# PCB.net
KiCad netlist of a schematic drawn in EAGLE
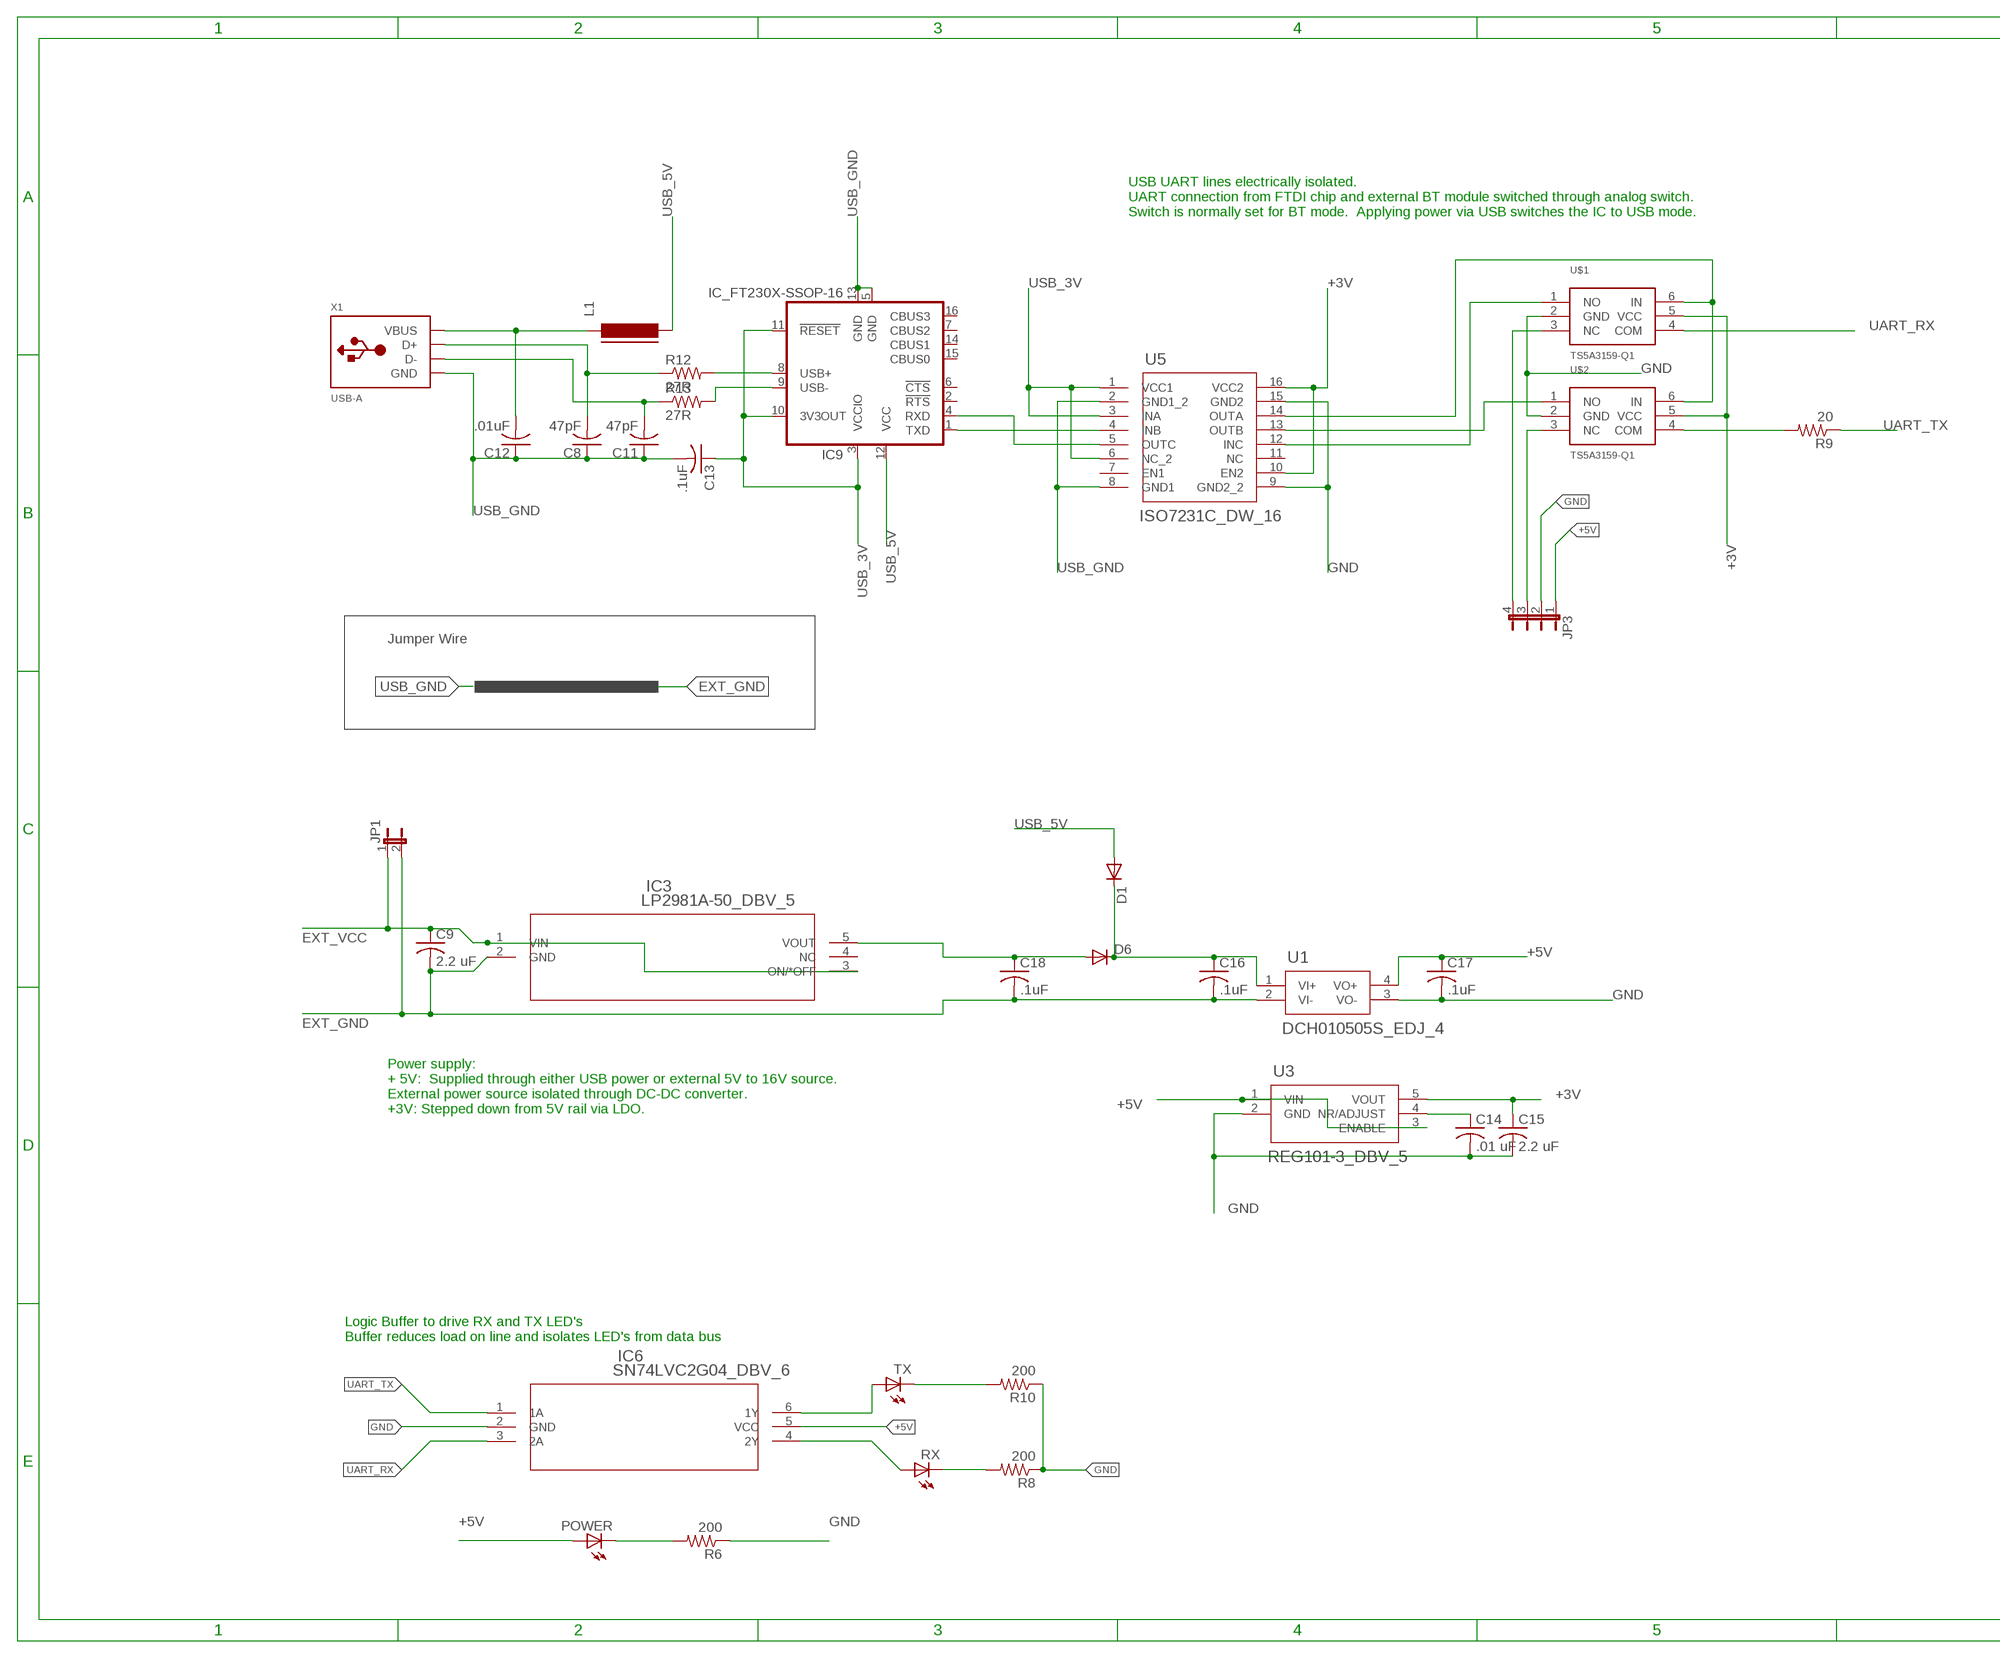
[diagram p0: schematic, sheet 1, part 1 of 2]
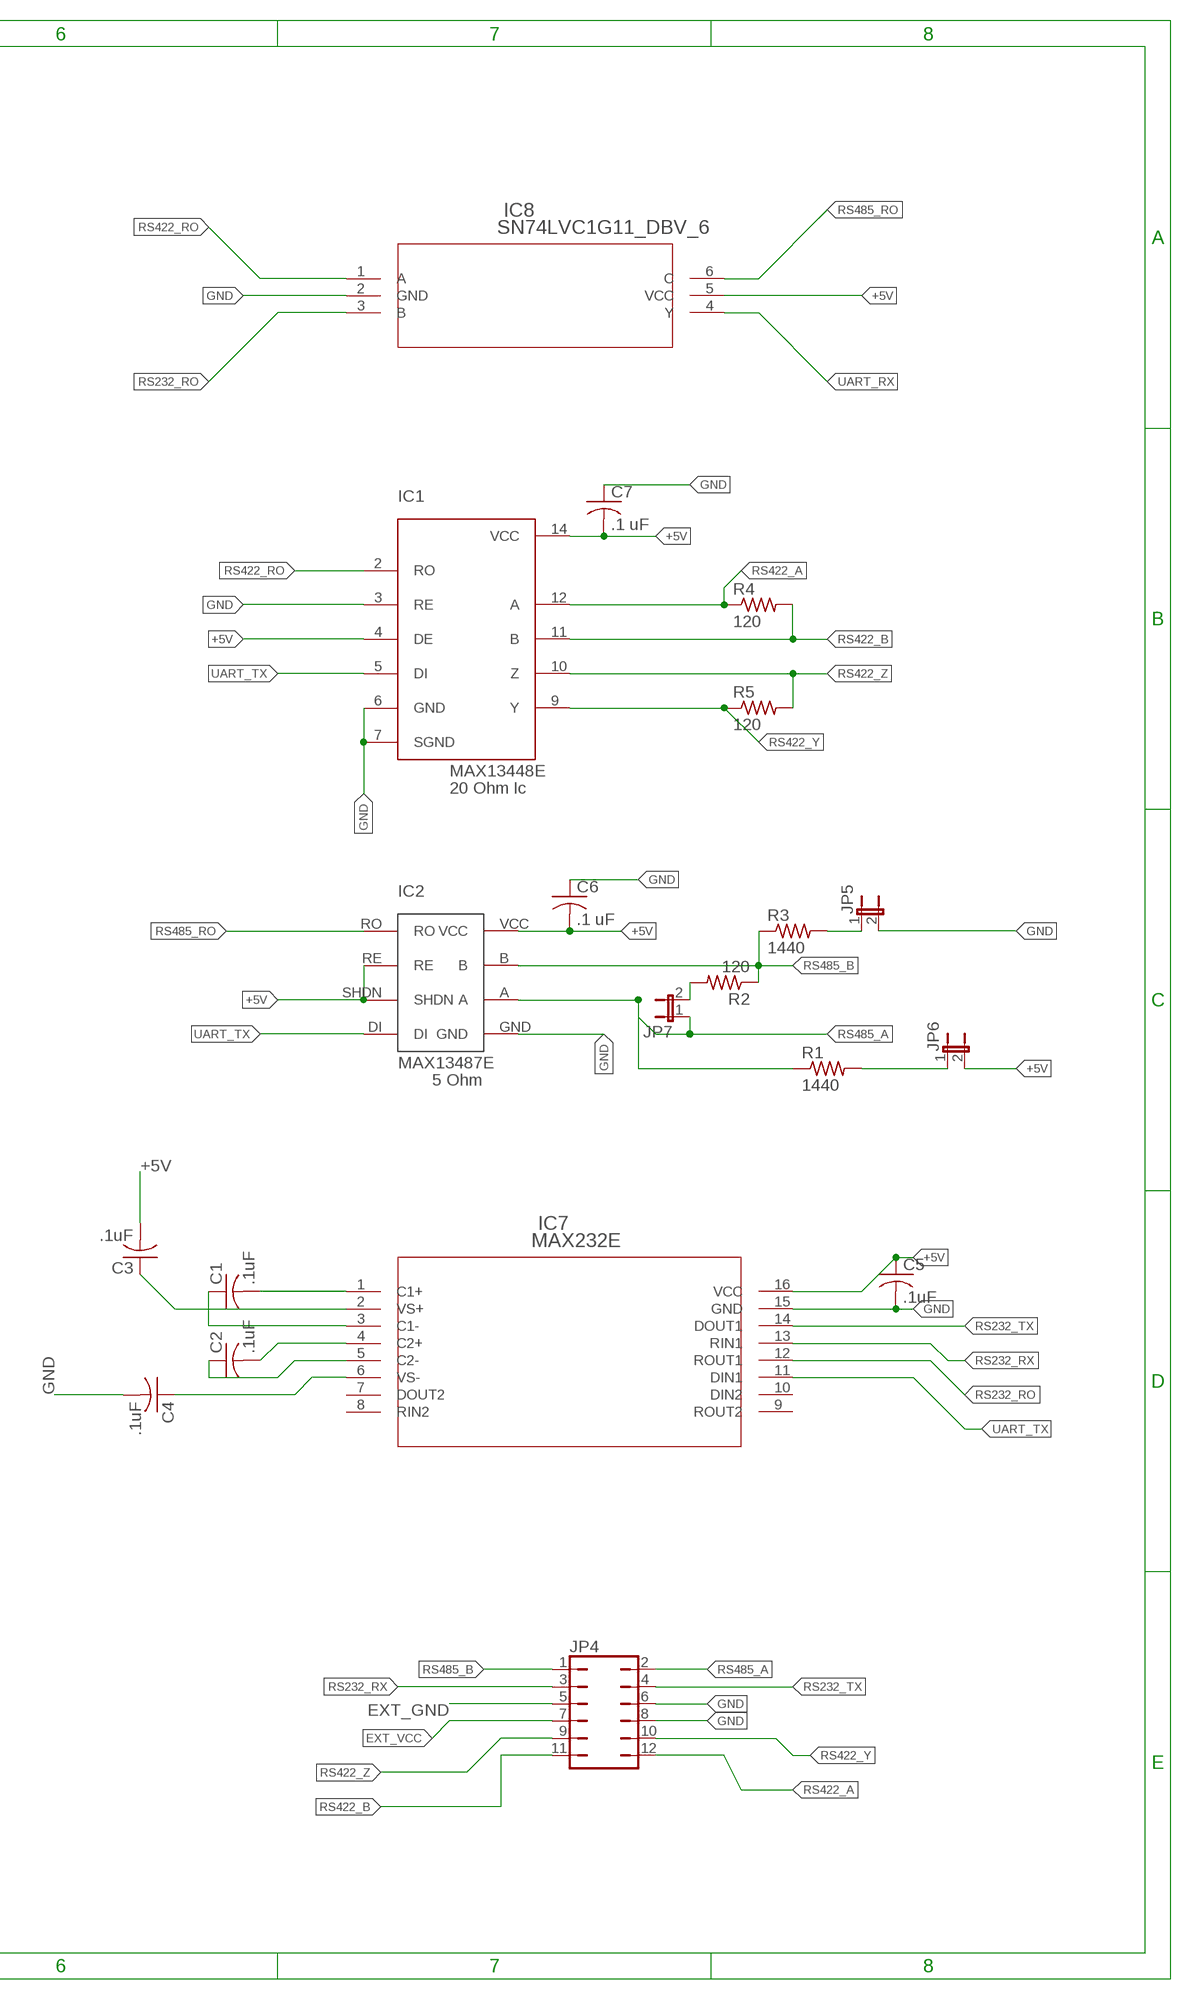
[diagram p1: schematic, sheet 1, part 2 of 2]

(export (version "E")
  (design (tool "Eeschema 10.0.6"))
  (components
    (comp (ref "C1")
      (value ".1uF")
      (footprint "eagle-import:C1206")
      (libsource (lib "eagle-import") (part "C-USC1206"))
    )
    (comp (ref "C2")
      (value ".1uF")
      (footprint "eagle-import:C1206")
      (libsource (lib "eagle-import") (part "C-USC1206"))
    )
    (comp (ref "C3")
      (value ".1uF")
      (footprint "eagle-import:C1206")
      (libsource (lib "eagle-import") (part "C-USC1206"))
    )
    (comp (ref "C4")
      (value ".1uF")
      (footprint "eagle-import:C1206")
      (libsource (lib "eagle-import") (part "C-USC1206"))
    )
    (comp (ref "C5")
      (value ".1uF")
      (footprint "eagle-import:C1206")
      (libsource (lib "eagle-import") (part "C-USC1206"))
    )
    (comp (ref "C6")
      (value ".1 uF")
      (footprint "eagle-import:C1206")
      (libsource (lib "eagle-import") (part "C-USC1206"))
    )
    (comp (ref "C7")
      (value ".1 uF")
      (footprint "eagle-import:C1206")
      (libsource (lib "eagle-import") (part "C-USC1206"))
    )
    (comp (ref "C8")
      (value "47pF")
      (footprint "eagle-import:C1206")
      (libsource (lib "eagle-import") (part "C-USC1206"))
    )
    (comp (ref "C9")
      (value "2.2 uF")
      (footprint "eagle-import:C1206")
      (libsource (lib "eagle-import") (part "C-USC1206"))
    )
    (comp (ref "C11")
      (value "47pF")
      (footprint "eagle-import:C1206")
      (libsource (lib "eagle-import") (part "C-USC1206"))
    )
    (comp (ref "C12")
      (value ".01uF")
      (footprint "eagle-import:C1206")
      (libsource (lib "eagle-import") (part "C-USC1206"))
    )
    (comp (ref "C13")
      (value ".1uF")
      (footprint "eagle-import:C1206")
      (libsource (lib "eagle-import") (part "C-USC1206"))
    )
    (comp (ref "C14")
      (value ".01 uF")
      (footprint "eagle-import:C1206")
      (libsource (lib "eagle-import") (part "C-USC1206"))
    )
    (comp (ref "C15")
      (value "2.2 uF")
      (footprint "eagle-import:C1206")
      (libsource (lib "eagle-import") (part "C-USC1206"))
    )
    (comp (ref "C16")
      (value ".1uF")
      (footprint "eagle-import:C1206")
      (libsource (lib "eagle-import") (part "C-USC1206"))
    )
    (comp (ref "C17")
      (value ".1uF")
      (footprint "eagle-import:C1206")
      (libsource (lib "eagle-import") (part "C-USC1206"))
    )
    (comp (ref "C18")
      (value ".1uF")
      (footprint "eagle-import:C1206")
      (libsource (lib "eagle-import") (part "C-USC1206"))
    )
    (comp (ref "D1")
      (value "DIODE-SOT23")
      (footprint "eagle-import:SOT-23")
      (libsource (lib "eagle-import") (part "DIODE-SOT23"))
    )
    (comp (ref "D6")
      (value "DIODE-SOT23")
      (footprint "eagle-import:SOT-23")
      (libsource (lib "eagle-import") (part "DIODE-SOT23"))
    )
    (comp (ref "IC1")
      (value "MAX13448E")
      (footprint "eagle-import:SO14(N)")
      (libsource (lib "eagle-import") (part "MAX13448E"))
    )
    (comp (ref "IC2")
      (value "MAX13487E")
      (footprint "eagle-import:MAX13487E")
      (libsource (lib "eagle-import") (part "MAX13487E"))
    )
    (comp (ref "IC3")
      (value "LP2981A-50_DBV_5")
      (footprint "eagle-import:DBV5")
      (fields
        (field (name "GENERIC_PART_NUMBER") "LP2981A-50")
        (field (name "MANUFACTURER") "Texas Instruments")
        (field (name "MANUFACTURER_PART_NUMBER") "lp2981a-50_dbv_5")
      )
      (libsource (lib "eagle-import") (part "LP2981A-50_DBV_5"))
    )
    (comp (ref "IC6")
      (value "SN74LVC2G04_DBV_6")
      (footprint "eagle-import:DBV6")
      (fields
        (field (name "GENERIC_PART_NUMBER") "SN74LVC2G04")
        (field (name "MANUFACTURER") "Texas Instruments")
        (field (name "MANUFACTURER_PART_NUMBER") "sn74lvc2g04_dbv_6")
      )
      (libsource (lib "eagle-import") (part "SN74LVC2G04_DBV_6"))
    )
    (comp (ref "IC7")
      (value "MAX232E")
      (footprint "eagle-import:D16")
      (fields
        (field (name "MANUFACTURER") "Texas Instruments")
        (field (name "MANUFACTURER_PART_NUMBER") "max232e_d_16")
      )
      (libsource (lib "eagle-import") (part "MAX232E_D_16"))
    )
    (comp (ref "IC8")
      (value "SN74LVC1G11_DBV_6")
      (footprint "eagle-import:DBV6")
      (fields
        (field (name "GENERIC_PART_NUMBER") "SN74LVC1G11")
        (field (name "MANUFACTURER") "Texas Instruments")
        (field (name "MANUFACTURER_PART_NUMBER") "sn74lvc1g11_dbv_6")
      )
      (libsource (lib "eagle-import") (part "SN74LVC1G11_DBV_6"))
    )
    (comp (ref "IC9")
      (value "IC_FT230X-SSOP-16")
      (footprint "eagle-import:SSOP-16-FTDI")
      (libsource (lib "eagle-import") (part "IC_FT230X-SSOP-16"))
    )
    (comp (ref "JP1")
      (value "JP1E")
      (footprint "eagle-import:JP1")
      (libsource (lib "eagle-import") (part "JP1E"))
    )
    (comp (ref "JP3")
      (value "JP4E")
      (footprint "eagle-import:JP4")
      (libsource (lib "eagle-import") (part "JP4E"))
    )
    (comp (ref "JP4")
      (value "JP6Q")
      (footprint "eagle-import:JP6Q")
      (libsource (lib "eagle-import") (part "JP6Q"))
    )
    (comp (ref "JP5")
      (value "JP1E")
      (footprint "eagle-import:JP1")
      (libsource (lib "eagle-import") (part "JP1E"))
    )
    (comp (ref "JP6")
      (value "JP1E")
      (footprint "eagle-import:JP1")
      (libsource (lib "eagle-import") (part "JP1E"))
    )
    (comp (ref "JP7")
      (value "JP1E")
      (footprint "eagle-import:JP1")
      (libsource (lib "eagle-import") (part "JP1E"))
    )
    (comp (ref "L1")
      (value "FERRITE-1206")
      (footprint "eagle-import:FB1206")
      (libsource (lib "eagle-import") (part "FERRITE-1206"))
    )
    (comp (ref "POWER")
      (value "LEDSMT1206")
      (footprint "eagle-import:1206")
      (libsource (lib "eagle-import") (part "LEDSMT1206"))
    )
    (comp (ref "R1")
      (value "1440")
      (footprint "eagle-import:M1206")
      (libsource (lib "eagle-import") (part "R-US_M1206"))
    )
    (comp (ref "R2")
      (value "120")
      (footprint "eagle-import:M1206")
      (libsource (lib "eagle-import") (part "R-US_M1206"))
    )
    (comp (ref "R3")
      (value "1440")
      (footprint "eagle-import:M1206")
      (libsource (lib "eagle-import") (part "R-US_M1206"))
    )
    (comp (ref "R4")
      (value "120")
      (footprint "eagle-import:R1206")
      (libsource (lib "eagle-import") (part "R-US_R1206"))
    )
    (comp (ref "R5")
      (value "120")
      (footprint "eagle-import:R1206")
      (libsource (lib "eagle-import") (part "R-US_R1206"))
    )
    (comp (ref "R6")
      (value "200")
      (footprint "eagle-import:M1206")
      (libsource (lib "eagle-import") (part "R-US_M1206"))
    )
    (comp (ref "R8")
      (value "200")
      (footprint "eagle-import:M1206")
      (libsource (lib "eagle-import") (part "R-US_M1206"))
    )
    (comp (ref "R9")
      (value "20")
      (footprint "eagle-import:M1206")
      (libsource (lib "eagle-import") (part "R-US_M1206"))
    )
    (comp (ref "R10")
      (value "200")
      (footprint "eagle-import:M1206")
      (libsource (lib "eagle-import") (part "R-US_M1206"))
    )
    (comp (ref "R12")
      (value "27R")
      (footprint "eagle-import:R1206")
      (libsource (lib "eagle-import") (part "R-US_R1206"))
    )
    (comp (ref "R13")
      (value "27R")
      (footprint "eagle-import:R1206")
      (libsource (lib "eagle-import") (part "R-US_R1206"))
    )
    (comp (ref "RX")
      (value "LEDSMT1206")
      (footprint "eagle-import:1206")
      (libsource (lib "eagle-import") (part "LEDSMT1206"))
    )
    (comp (ref "TX")
      (value "LEDSMT1206")
      (footprint "eagle-import:1206")
      (libsource (lib "eagle-import") (part "LEDSMT1206"))
    )
    (comp (ref "U$1")
      (value "TS5A3159-Q1")
      (footprint "eagle-import:DBV6")
      (libsource (lib "eagle-import") (part "TS5A3159-Q1"))
    )
    (comp (ref "U$2")
      (value "TS5A3159-Q1")
      (footprint "eagle-import:DBV6")
      (libsource (lib "eagle-import") (part "TS5A3159-Q1"))
    )
    (comp (ref "U1")
      (value "DCH010505S_EDJ_4")
      (footprint "eagle-import:EDJ4")
      (fields
        (field (name "GENERIC_PART_NUMBER") "DCH010505S")
        (field (name "MANUFACTURER") "Texas Instruments")
        (field (name "MANUFACTURER_PART_NUMBER") "dch010505s_edj_4")
      )
      (libsource (lib "eagle-import") (part "DCH010505S_EDJ_4"))
    )
    (comp (ref "U3")
      (value "REG101-3_DBV_5")
      (footprint "eagle-import:DBV5")
      (fields
        (field (name "GENERIC_PART_NUMBER") "REG101-3")
        (field (name "MANUFACTURER") "Texas Instruments")
        (field (name "MANUFACTURER_PART_NUMBER") "reg101-3_dbv_5")
      )
      (libsource (lib "eagle-import") (part "REG101-3_DBV_5"))
    )
    (comp (ref "U5")
      (value "ISO7231C_DW_16")
      (footprint "eagle-import:DW16")
      (fields
        (field (name "GENERIC_PART_NUMBER") "ISO7231C")
        (field (name "MANUFACTURER") "Texas Instruments")
        (field (name "MANUFACTURER_PART_NUMBER") "iso7231c_dw_16")
      )
      (libsource (lib "eagle-import") (part "ISO7231C_DW_16"))
    )
    (comp (ref "X1")
      (value "USB-A")
      (footprint "eagle-import:MOLEX_480371000")
      (libsource (lib "eagle-import") (part "USB-A"))
    )
  )
  (nets
    (net (code "1") (name "+5V") (class "Default")
      (node (ref "C17") (pin "1") (pinfunction "1_1") (pintype "passive"))
      (node (ref "C3") (pin "2") (pinfunction "2_2") (pintype "passive"))
      (node (ref "C5") (pin "1") (pinfunction "1_1") (pintype "passive"))
      (node (ref "C6") (pin "2") (pinfunction "2_2") (pintype "passive"))
      (node (ref "C7") (pin "2") (pinfunction "2_2") (pintype "passive"))
      (node (ref "IC1") (pin "14") (pinfunction "VCC_14") (pintype "bidirectional"))
      (node (ref "IC1") (pin "4") (pinfunction "DE_4") (pintype "bidirectional"))
      (node (ref "IC2") (pin "RE") (pinfunction "RE_RE") (pintype "bidirectional"))
      (node (ref "IC2") (pin "SHDN") (pinfunction "SHDN_SHDN") (pintype "bidirectional"))
      (node (ref "IC2") (pin "VCC") (pinfunction "VCC_VCC") (pintype "bidirectional"))
      (node (ref "IC6") (pin "5") (pinfunction "VCC_5") (pintype "power_in"))
      (node (ref "IC7") (pin "16") (pinfunction "VCC_16") (pintype "power_in"))
      (node (ref "IC8") (pin "5") (pinfunction "VCC_5") (pintype "power_in"))
      (node (ref "JP3") (pin "1") (pinfunction "1_1") (pintype "passive"))
      (node (ref "JP6") (pin "2") (pinfunction "2_2") (pintype "passive"))
      (node (ref "POWER") (pin "A") (pinfunction "A_A") (pintype "passive"))
      (node (ref "U1") (pin "4") (pinfunction "VO+_4") (pintype "output"))
      (node (ref "U3") (pin "1") (pinfunction "VIN_1") (pintype "input"))
      (node (ref "U3") (pin "3") (pinfunction "ENABLE_3") (pintype "passive"))
    )
    (net (code "2") (name "/+3V") (class "Default")
      (node (ref "C15") (pin "1") (pinfunction "1_1") (pintype "passive"))
      (node (ref "U$1") (pin "5") (pinfunction "VCC_5") (pintype "power_in"))
      (node (ref "U$2") (pin "5") (pinfunction "VCC_5") (pintype "power_in"))
      (node (ref "U3") (pin "5") (pinfunction "VOUT_5") (pintype "output"))
      (node (ref "U5") (pin "10") (pinfunction "EN2_10") (pintype "passive"))
      (node (ref "U5") (pin "16") (pinfunction "VCC2_16") (pintype "power_in"))
    )
    (net (code "3") (name "/USB_3V") (class "Default")
      (node (ref "C13") (pin "1") (pinfunction "1_1") (pintype "passive"))
      (node (ref "IC9") (pin "10") (pinfunction "3V3OUT_10") (pintype "power_in"))
      (node (ref "IC9") (pin "11") (pinfunction "~{RESET}_11") (pintype "bidirectional"))
      (node (ref "IC9") (pin "3") (pinfunction "VCCIO_3") (pintype "power_in"))
      (node (ref "U5") (pin "1") (pinfunction "VCC1_1") (pintype "power_in"))
      (node (ref "U5") (pin "3") (pinfunction "INA_3") (pintype "input"))
      (node (ref "U5") (pin "6") (pinfunction "NC_2_6") (pintype "passive"))
    )
    (net (code "4") (name "/USB_5V") (class "Default")
      (node (ref "D1") (pin "1") (pinfunction "A_1") (pintype "passive"))
      (node (ref "IC9") (pin "12") (pinfunction "VCC_12") (pintype "power_in"))
      (node (ref "L1") (pin "2") (pinfunction "2_2") (pintype "passive"))
    )
    (net (code "5") (name "EXT_GND") (class "Default")
      (node (ref "C16") (pin "2") (pinfunction "2_2") (pintype "passive"))
      (node (ref "C18") (pin "2") (pinfunction "2_2") (pintype "passive"))
      (node (ref "C9") (pin "2") (pinfunction "2_2") (pintype "passive"))
      (node (ref "IC3") (pin "2") (pinfunction "GND_2") (pintype "power_in"))
      (node (ref "JP1") (pin "2") (pinfunction "2_2") (pintype "passive"))
      (node (ref "JP4") (pin "5") (pinfunction "5_5") (pintype "passive"))
      (node (ref "U1") (pin "2") (pinfunction "VI-_2") (pintype "input"))
    )
    (net (code "6") (name "EXT_VCC") (class "Default")
      (node (ref "C9") (pin "1") (pinfunction "1_1") (pintype "passive"))
      (node (ref "IC3") (pin "1") (pinfunction "VIN_1") (pintype "input"))
      (node (ref "IC3") (pin "3") (pinfunction "ON/*OFF_3") (pintype "passive"))
      (node (ref "JP1") (pin "1") (pinfunction "1_1") (pintype "passive"))
      (node (ref "JP4") (pin "7") (pinfunction "7_7") (pintype "passive"))
    )
    (net (code "7") (name "GND") (class "Default")
      (node (ref "C14") (pin "2") (pinfunction "2_2") (pintype "passive"))
      (node (ref "C15") (pin "2") (pinfunction "2_2") (pintype "passive"))
      (node (ref "C17") (pin "2") (pinfunction "2_2") (pintype "passive"))
      (node (ref "C4") (pin "2") (pinfunction "2_2") (pintype "passive"))
      (node (ref "C5") (pin "2") (pinfunction "2_2") (pintype "passive"))
      (node (ref "C6") (pin "1") (pinfunction "1_1") (pintype "passive"))
      (node (ref "C7") (pin "1") (pinfunction "1_1") (pintype "passive"))
      (node (ref "IC1") (pin "3") (pinfunction "RE_3") (pintype "bidirectional"))
      (node (ref "IC1") (pin "6") (pinfunction "GND_6") (pintype "bidirectional"))
      (node (ref "IC1") (pin "7") (pinfunction "SGND_7") (pintype "bidirectional"))
      (node (ref "IC2") (pin "GND") (pinfunction "GND_GND") (pintype "bidirectional"))
      (node (ref "IC6") (pin "2") (pinfunction "GND_2") (pintype "power_in"))
      (node (ref "IC7") (pin "15") (pinfunction "GND_15") (pintype "power_in"))
      (node (ref "IC8") (pin "2") (pinfunction "GND_2") (pintype "power_in"))
      (node (ref "JP3") (pin "2") (pinfunction "2_2") (pintype "passive"))
      (node (ref "JP4") (pin "6") (pinfunction "6_6") (pintype "passive"))
      (node (ref "JP4") (pin "8") (pinfunction "8_8") (pintype "passive"))
      (node (ref "JP5") (pin "2") (pinfunction "2_2") (pintype "passive"))
      (node (ref "R10") (pin "1") (pinfunction "1_1") (pintype "passive"))
      (node (ref "R6") (pin "1") (pinfunction "1_1") (pintype "passive"))
      (node (ref "R8") (pin "1") (pinfunction "1_1") (pintype "passive"))
      (node (ref "U$1") (pin "2") (pinfunction "GND_2") (pintype "power_in"))
      (node (ref "U$2") (pin "2") (pinfunction "GND_2") (pintype "power_in"))
      (node (ref "U1") (pin "3") (pinfunction "VO-_3") (pintype "output"))
      (node (ref "U3") (pin "2") (pinfunction "GND_2") (pintype "power_in"))
      (node (ref "U5") (pin "15") (pinfunction "GND2_15") (pintype "power_in"))
      (node (ref "U5") (pin "9") (pinfunction "GND2_2_9") (pintype "power_in"))
    )
    (net (code "8") (name "Net-(D1-C)") (class "Default")
      (node (ref "C16") (pin "1") (pinfunction "1_1") (pintype "passive"))
      (node (ref "D1") (pin "3") (pinfunction "C_3") (pintype "passive"))
      (node (ref "D6") (pin "3") (pinfunction "C_3") (pintype "passive"))
      (node (ref "U1") (pin "1") (pinfunction "VI+_1") (pintype "input"))
    )
    (net (code "9") (name "Net-(D6-A)") (class "Default")
      (node (ref "C18") (pin "1") (pinfunction "1_1") (pintype "passive"))
      (node (ref "D6") (pin "1") (pinfunction "A_1") (pintype "passive"))
      (node (ref "IC3") (pin "5") (pinfunction "VOUT_5") (pintype "output"))
    )
    (net (code "10") (name "Net-(IC6-1Y)") (class "Default")
      (node (ref "IC6") (pin "6") (pinfunction "1Y_6") (pintype "output"))
      (node (ref "TX") (pin "A") (pinfunction "A_A") (pintype "passive"))
    )
    (net (code "11") (name "Net-(IC6-2Y)") (class "Default")
      (node (ref "IC6") (pin "4") (pinfunction "2Y_4") (pintype "output"))
      (node (ref "RX") (pin "A") (pinfunction "A_A") (pintype "passive"))
    )
    (net (code "12") (name "Net-(IC7-C1+)") (class "Default")
      (node (ref "C1") (pin "2") (pinfunction "2_2") (pintype "passive"))
      (node (ref "IC7") (pin "1") (pinfunction "C1+_1") (pintype "passive"))
    )
    (net (code "13") (name "Net-(IC7-C1-)") (class "Default")
      (node (ref "C1") (pin "1") (pinfunction "1_1") (pintype "passive"))
      (node (ref "IC7") (pin "3") (pinfunction "C1-_3") (pintype "passive"))
    )
    (net (code "14") (name "Net-(IC7-C2+)") (class "Default")
      (node (ref "C2") (pin "2") (pinfunction "2_2") (pintype "passive"))
      (node (ref "IC7") (pin "4") (pinfunction "C2+_4") (pintype "passive"))
    )
    (net (code "15") (name "Net-(IC7-C2-)") (class "Default")
      (node (ref "C2") (pin "1") (pinfunction "1_1") (pintype "passive"))
      (node (ref "IC7") (pin "5") (pinfunction "C2-_5") (pintype "passive"))
    )
    (net (code "16") (name "Net-(IC7-VS+)") (class "Default")
      (node (ref "C3") (pin "1") (pinfunction "1_1") (pintype "passive"))
      (node (ref "IC7") (pin "2") (pinfunction "VS+_2") (pintype "power_in"))
    )
    (net (code "17") (name "Net-(IC7-VS-)") (class "Default")
      (node (ref "C4") (pin "1") (pinfunction "1_1") (pintype "passive"))
      (node (ref "IC7") (pin "6") (pinfunction "VS-_6") (pintype "power_in"))
    )
    (net (code "18") (name "Net-(IC9-RXD)") (class "Default")
      (node (ref "IC9") (pin "4") (pinfunction "RXD_4") (pintype "input"))
      (node (ref "U5") (pin "5") (pinfunction "OUTC_5") (pintype "output"))
    )
    (net (code "19") (name "Net-(IC9-TXD)") (class "Default")
      (node (ref "IC9") (pin "1") (pinfunction "TXD_1") (pintype "output"))
      (node (ref "U5") (pin "4") (pinfunction "INB_4") (pintype "input"))
    )
    (net (code "20") (name "Net-(IC9-USB+)") (class "Default")
      (node (ref "IC9") (pin "8") (pinfunction "USB+_8") (pintype "output"))
      (node (ref "R12") (pin "2") (pinfunction "2_2") (pintype "passive"))
    )
    (net (code "21") (name "Net-(IC9-USB-)") (class "Default")
      (node (ref "IC9") (pin "9") (pinfunction "USB-_9") (pintype "input"))
      (node (ref "R13") (pin "2") (pinfunction "2_2") (pintype "passive"))
    )
    (net (code "22") (name "Net-(JP5-Pad1)") (class "Default")
      (node (ref "JP5") (pin "1") (pinfunction "1_1") (pintype "passive"))
      (node (ref "R3") (pin "2") (pinfunction "2_2") (pintype "passive"))
    )
    (net (code "23") (name "Net-(JP6-Pad1)") (class "Default")
      (node (ref "JP6") (pin "1") (pinfunction "1_1") (pintype "passive"))
      (node (ref "R1") (pin "2") (pinfunction "2_2") (pintype "passive"))
    )
    (net (code "24") (name "Net-(JP7-Pad2)") (class "Default")
      (node (ref "JP7") (pin "2") (pinfunction "2_2") (pintype "passive"))
      (node (ref "R2") (pin "2") (pinfunction "2_2") (pintype "passive"))
    )
    (net (code "25") (name "Net-(POWER-PadC)") (class "Default")
      (node (ref "POWER") (pin "C") (pinfunction "C_C") (pintype "passive"))
      (node (ref "R6") (pin "2") (pinfunction "2_2") (pintype "passive"))
    )
    (net (code "26") (name "Net-(R8-Pad2)") (class "Default")
      (node (ref "R8") (pin "2") (pinfunction "2_2") (pintype "passive"))
      (node (ref "RX") (pin "C") (pinfunction "C_C") (pintype "passive"))
    )
    (net (code "27") (name "Net-(R10-Pad2)") (class "Default")
      (node (ref "R10") (pin "2") (pinfunction "2_2") (pintype "passive"))
      (node (ref "TX") (pin "C") (pinfunction "C_C") (pintype "passive"))
    )
    (net (code "28") (name "Net-(U$1-IN)") (class "Default")
      (node (ref "U$1") (pin "6") (pinfunction "IN_6") (pintype "power_in"))
      (node (ref "U$2") (pin "6") (pinfunction "IN_6") (pintype "power_in"))
      (node (ref "U5") (pin "14") (pinfunction "OUTA_14") (pintype "output"))
    )
    (net (code "29") (name "Net-(U$1-NC)") (class "Default")
      (node (ref "JP3") (pin "4") (pinfunction "4_4") (pintype "passive"))
      (node (ref "U$1") (pin "3") (pinfunction "NC_3") (pintype "power_in"))
    )
    (net (code "30") (name "Net-(U$1-NO)") (class "Default")
      (node (ref "U$1") (pin "1") (pinfunction "NO_1") (pintype "power_in"))
      (node (ref "U5") (pin "12") (pinfunction "INC_12") (pintype "input"))
    )
    (net (code "31") (name "Net-(U$2-COM)") (class "Default")
      (node (ref "R9") (pin "2") (pinfunction "2_2") (pintype "passive"))
      (node (ref "U$2") (pin "4") (pinfunction "COM_4") (pintype "power_in"))
    )
    (net (code "32") (name "Net-(U$2-NC)") (class "Default")
      (node (ref "JP3") (pin "3") (pinfunction "3_3") (pintype "passive"))
      (node (ref "U$2") (pin "3") (pinfunction "NC_3") (pintype "power_in"))
    )
    (net (code "33") (name "Net-(U$2-NO)") (class "Default")
      (node (ref "U$2") (pin "1") (pinfunction "NO_1") (pintype "power_in"))
      (node (ref "U5") (pin "13") (pinfunction "OUTB_13") (pintype "output"))
    )
    (net (code "34") (name "Net-(U3-NR{slash}ADJUST)") (class "Default")
      (node (ref "C14") (pin "1") (pinfunction "1_1") (pintype "passive"))
      (node (ref "U3") (pin "4") (pinfunction "NR/ADJUST_4") (pintype "bidirectional"))
    )
    (net (code "35") (name "Net-(X1-D+)") (class "Default")
      (node (ref "C8") (pin "2") (pinfunction "2_2") (pintype "passive"))
      (node (ref "R12") (pin "1") (pinfunction "1_1") (pintype "passive"))
      (node (ref "X1") (pin "3") (pinfunction "D+_3") (pintype "bidirectional"))
    )
    (net (code "36") (name "Net-(X1-D-)") (class "Default")
      (node (ref "C11") (pin "2") (pinfunction "2_2") (pintype "passive"))
      (node (ref "R13") (pin "1") (pinfunction "1_1") (pintype "passive"))
      (node (ref "X1") (pin "2") (pinfunction "D-_2") (pintype "bidirectional"))
    )
    (net (code "37") (name "Net-(X1-VBUS)") (class "Default")
      (node (ref "C12") (pin "2") (pinfunction "2_2") (pintype "passive"))
      (node (ref "L1") (pin "1") (pinfunction "1_1") (pintype "passive"))
      (node (ref "X1") (pin "1") (pinfunction "VBUS_1") (pintype "power_in"))
    )
    (net (code "38") (name "RS232_RO") (class "Default")
      (node (ref "IC7") (pin "12") (pinfunction "ROUT1_12") (pintype "output"))
      (node (ref "IC8") (pin "3") (pinfunction "B_3") (pintype "input"))
    )
    (net (code "39") (name "RS232_RX") (class "Default")
      (node (ref "IC7") (pin "13") (pinfunction "RIN1_13") (pintype "input"))
      (node (ref "JP4") (pin "3") (pinfunction "3_3") (pintype "passive"))
    )
    (net (code "40") (name "RS232_TX") (class "Default")
      (node (ref "IC7") (pin "14") (pinfunction "DOUT1_14") (pintype "output"))
      (node (ref "JP4") (pin "4") (pinfunction "4_4") (pintype "passive"))
    )
    (net (code "41") (name "RS422_A") (class "Default")
      (node (ref "IC1") (pin "12") (pinfunction "A_12") (pintype "bidirectional"))
      (node (ref "JP4") (pin "12") (pinfunction "12_12") (pintype "passive"))
      (node (ref "R4") (pin "1") (pinfunction "1_1") (pintype "passive"))
    )
    (net (code "42") (name "RS422_B") (class "Default")
      (node (ref "IC1") (pin "11") (pinfunction "B_11") (pintype "bidirectional"))
      (node (ref "JP4") (pin "11") (pinfunction "11_11") (pintype "passive"))
      (node (ref "R4") (pin "2") (pinfunction "2_2") (pintype "passive"))
    )
    (net (code "43") (name "RS422_RO") (class "Default")
      (node (ref "IC1") (pin "2") (pinfunction "RO_2") (pintype "bidirectional"))
      (node (ref "IC8") (pin "1") (pinfunction "A_1") (pintype "input"))
    )
    (net (code "44") (name "RS422_Y") (class "Default")
      (node (ref "IC1") (pin "9") (pinfunction "Y_9") (pintype "bidirectional"))
      (node (ref "JP4") (pin "10") (pinfunction "10_10") (pintype "passive"))
      (node (ref "R5") (pin "1") (pinfunction "1_1") (pintype "passive"))
    )
    (net (code "45") (name "RS422_Z") (class "Default")
      (node (ref "IC1") (pin "10") (pinfunction "Z_10") (pintype "bidirectional"))
      (node (ref "JP4") (pin "9") (pinfunction "9_9") (pintype "passive"))
      (node (ref "R5") (pin "2") (pinfunction "2_2") (pintype "passive"))
    )
    (net (code "46") (name "RS485_A") (class "Default")
      (node (ref "IC2") (pin "A") (pinfunction "A_A") (pintype "bidirectional"))
      (node (ref "JP4") (pin "2") (pinfunction "2_2") (pintype "passive"))
      (node (ref "JP7") (pin "1") (pinfunction "1_1") (pintype "passive"))
      (node (ref "R1") (pin "1") (pinfunction "1_1") (pintype "passive"))
    )
    (net (code "47") (name "RS485_B") (class "Default")
      (node (ref "IC2") (pin "B") (pinfunction "B_B") (pintype "bidirectional"))
      (node (ref "JP4") (pin "1") (pinfunction "1_1") (pintype "passive"))
      (node (ref "R2") (pin "1") (pinfunction "1_1") (pintype "passive"))
      (node (ref "R3") (pin "1") (pinfunction "1_1") (pintype "passive"))
    )
    (net (code "48") (name "RS485_RO") (class "Default")
      (node (ref "IC2") (pin "RO") (pinfunction "RO_RO") (pintype "bidirectional"))
      (node (ref "IC8") (pin "6") (pinfunction "C_6") (pintype "input"))
    )
    (net (code "49") (name "UART_RX") (class "Default")
      (node (ref "IC6") (pin "3") (pinfunction "2A_3") (pintype "input"))
      (node (ref "IC8") (pin "4") (pinfunction "Y_4") (pintype "output"))
      (node (ref "U$1") (pin "4") (pinfunction "COM_4") (pintype "power_in"))
    )
    (net (code "50") (name "UART_TX") (class "Default")
      (node (ref "IC1") (pin "5") (pinfunction "DI_5") (pintype "bidirectional"))
      (node (ref "IC2") (pin "DI") (pinfunction "DI_DI") (pintype "bidirectional"))
      (node (ref "IC6") (pin "1") (pinfunction "1A_1") (pintype "input"))
      (node (ref "IC7") (pin "11") (pinfunction "DIN1_11") (pintype "input"))
      (node (ref "R9") (pin "1") (pinfunction "1_1") (pintype "passive"))
    )
    (net (code "51") (name "USB_GND") (class "Default")
      (node (ref "C11") (pin "1") (pinfunction "1_1") (pintype "passive"))
      (node (ref "C12") (pin "1") (pinfunction "1_1") (pintype "passive"))
      (node (ref "C13") (pin "2") (pinfunction "2_2") (pintype "passive"))
      (node (ref "C8") (pin "1") (pinfunction "1_1") (pintype "passive"))
      (node (ref "IC9") (pin "13") (pinfunction "GND_13") (pintype "power_in"))
      (node (ref "IC9") (pin "5") (pinfunction "GND_5") (pintype "power_in"))
      (node (ref "U5") (pin "2") (pinfunction "GND1_2_2") (pintype "power_in"))
      (node (ref "U5") (pin "8") (pinfunction "GND1_8") (pintype "power_in"))
      (node (ref "X1") (pin "4") (pinfunction "GND_4") (pintype "power_in"))
    )
    (net (code "52") (name "unconnected-(IC3-NC-Pad4)") (class "Default")
      (node (ref "IC3") (pin "4") (pinfunction "NC_4") (pintype "passive"))
    )
    (net (code "53") (name "unconnected-(IC7-DIN2-Pad10)") (class "Default")
      (node (ref "IC7") (pin "10") (pinfunction "DIN2_10") (pintype "input"))
    )
    (net (code "54") (name "unconnected-(IC7-DOUT2-Pad7)") (class "Default")
      (node (ref "IC7") (pin "7") (pinfunction "DOUT2_7") (pintype "output"))
    )
    (net (code "55") (name "unconnected-(IC7-RIN2-Pad8)") (class "Default")
      (node (ref "IC7") (pin "8") (pinfunction "RIN2_8") (pintype "input"))
    )
    (net (code "56") (name "unconnected-(IC7-ROUT2-Pad9)") (class "Default")
      (node (ref "IC7") (pin "9") (pinfunction "ROUT2_9") (pintype "output"))
    )
    (net (code "57") (name "unconnected-(IC9-CBUS0-Pad15)") (class "Default")
      (node (ref "IC9") (pin "15") (pinfunction "CBUS0_15") (pintype "bidirectional"))
    )
    (net (code "58") (name "unconnected-(IC9-CBUS1-Pad14)") (class "Default")
      (node (ref "IC9") (pin "14") (pinfunction "CBUS1_14") (pintype "bidirectional"))
    )
    (net (code "59") (name "unconnected-(IC9-CBUS2-Pad7)") (class "Default")
      (node (ref "IC9") (pin "7") (pinfunction "CBUS2_7") (pintype "bidirectional"))
    )
    (net (code "60") (name "unconnected-(IC9-CBUS3-Pad16)") (class "Default")
      (node (ref "IC9") (pin "16") (pinfunction "CBUS3_16") (pintype "bidirectional"))
    )
    (net (code "61") (name "unconnected-(IC9-~{CTS}-Pad6)") (class "Default")
      (node (ref "IC9") (pin "6") (pinfunction "~{CTS}_6") (pintype "bidirectional"))
    )
    (net (code "62") (name "unconnected-(IC9-~{RTS}-Pad2)") (class "Default")
      (node (ref "IC9") (pin "2") (pinfunction "~{RTS}_2") (pintype "bidirectional"))
    )
    (net (code "63") (name "unconnected-(U5-EN1-Pad7)") (class "Default")
      (node (ref "U5") (pin "7") (pinfunction "EN1_7") (pintype "passive"))
    )
    (net (code "64") (name "unconnected-(U5-NC-Pad11)") (class "Default")
      (node (ref "U5") (pin "11") (pinfunction "NC_11") (pintype "passive"))
    )
  )
)
